# lcd_duffle_pth_mk_6.net
KiCad netlist of a schematic drawn in EAGLE
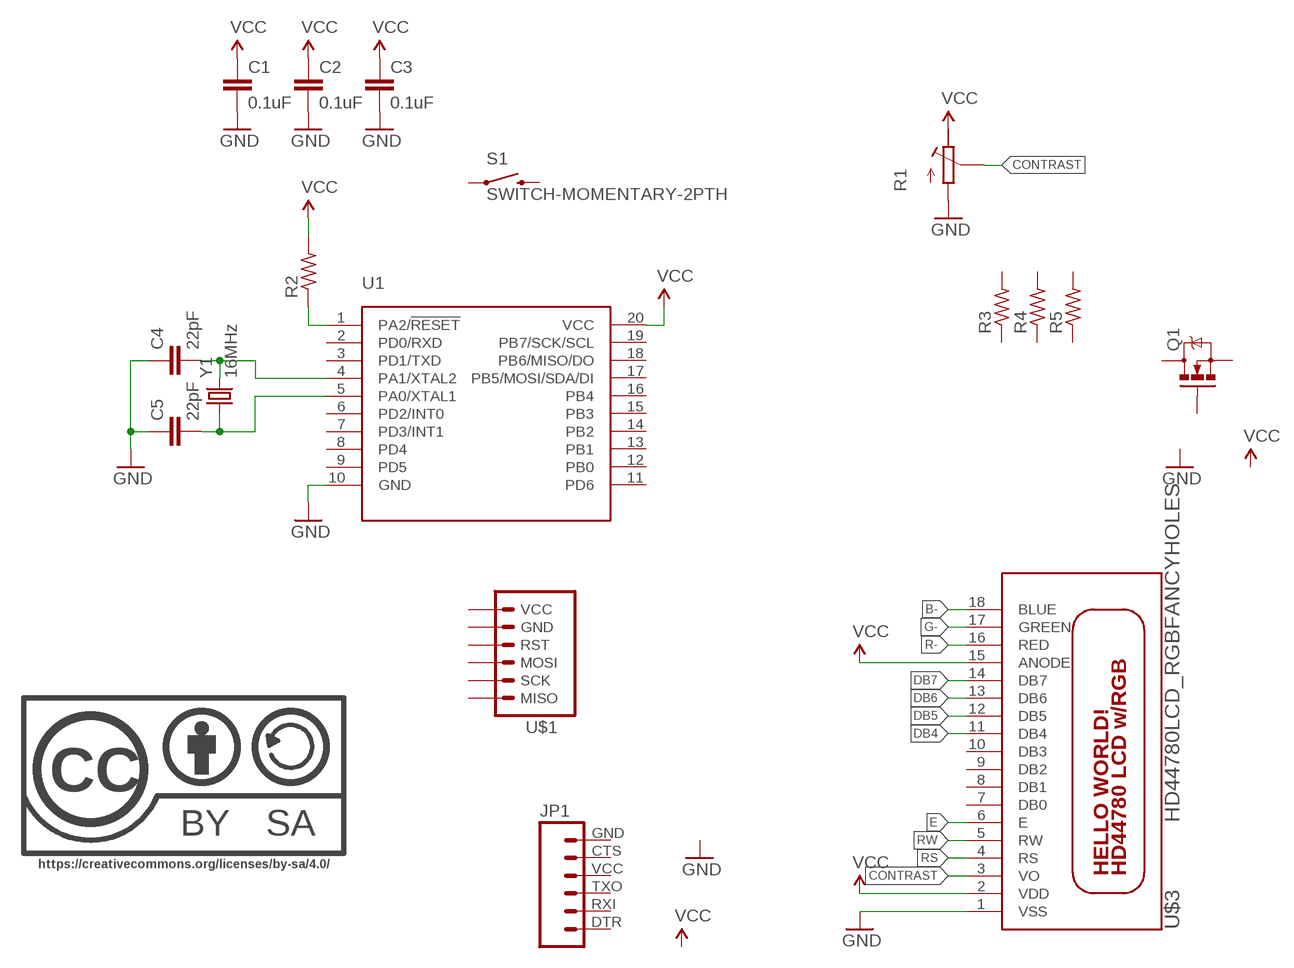
[diagram p0: schematic, sheet 1]

(export (version "E")
  (design (tool "Eeschema 10.0.6"))
  (components
    (comp (ref "C1")
      (value "0.1uF")
      (footprint "eagle-import:C025-024X044")
      (libsource (lib "eagle-import") (part "CAPACITOR-CERAMIC025-024X044"))
    )
    (comp (ref "C2")
      (value "0.1uF")
      (footprint "eagle-import:C025-024X044")
      (libsource (lib "eagle-import") (part "CAPACITOR-CERAMIC025-024X044"))
    )
    (comp (ref "C3")
      (value "0.1uF")
      (footprint "eagle-import:C025-024X044")
      (libsource (lib "eagle-import") (part "CAPACITOR-CERAMIC025-024X044"))
    )
    (comp (ref "C4")
      (value "22pF")
      (footprint "eagle-import:C025-024X044")
      (libsource (lib "eagle-import") (part "CAPACITOR-CERAMIC025-024X044"))
    )
    (comp (ref "C5")
      (value "22pF")
      (footprint "eagle-import:C025-024X044")
      (libsource (lib "eagle-import") (part "CAPACITOR-CERAMIC025-024X044"))
    )
    (comp (ref "JP1")
      (value "FTDI_BASICPTH-TINY-TEXT")
      (footprint "eagle-import:FTDI_TINY_TXT")
      (libsource (lib "eagle-import") (part "FTDI_BASICPTH-TINY-TEXT"))
    )
    (comp (ref "Q1")
      (value "MOSFET-NCHANNEL2N7000")
      (footprint "eagle-import:TO-92")
      (libsource (lib "eagle-import") (part "MOSFET-NCHANNEL2N7000"))
    )
    (comp (ref "R1")
      (value "POTENTIOMETERTHUMBWHEEL-16MM")
      (footprint "eagle-import:POT-THUMBWHEEL")
      (libsource (lib "eagle-import") (part "POTENTIOMETERTHUMBWHEEL-16MM"))
    )
    (comp (ref "R2")
      (value "RESISTORPTH-AXIAL-6.35MM")
      (footprint "eagle-import:RESISTOR-AXIAL-PTH-6.35MM")
      (libsource (lib "eagle-import") (part "RESISTORPTH-AXIAL-6.35MM"))
    )
    (comp (ref "R3")
      (value "RESISTORPTH-AXIAL-6.35MM")
      (footprint "eagle-import:RESISTOR-AXIAL-PTH-6.35MM")
      (libsource (lib "eagle-import") (part "RESISTORPTH-AXIAL-6.35MM"))
    )
    (comp (ref "R4")
      (value "RESISTORPTH-AXIAL-6.35MM")
      (footprint "eagle-import:RESISTOR-AXIAL-PTH-6.35MM")
      (libsource (lib "eagle-import") (part "RESISTORPTH-AXIAL-6.35MM"))
    )
    (comp (ref "R5")
      (value "RESISTORPTH-AXIAL-6.35MM")
      (footprint "eagle-import:RESISTOR-AXIAL-PTH-6.35MM")
      (libsource (lib "eagle-import") (part "RESISTORPTH-AXIAL-6.35MM"))
    )
    (comp (ref "S1")
      (value "SWITCH-MOMENTARY-2PTH")
      (footprint "eagle-import:TACTILE-PTH")
      (libsource (lib "eagle-import") (part "SWITCH-MOMENTARY-2PTH"))
    )
    (comp (ref "U$1")
      (value "AVR_MINI_PROGJST-XH-RA-PTH")
      (footprint "eagle-import:AVR_MINI_PROG_JST_XH_RA")
      (libsource (lib "eagle-import") (part "AVR_MINI_PROGJST-XH-RA-PTH"))
    )
    (comp (ref "U$2")
      (value "CC-BY-SA-4.0NO-URL")
      (footprint "eagle-import:CC-BY-SA-4.0-NO-URL")
      (libsource (lib "eagle-import") (part "CC-BY-SA-4.0NO-URL"))
    )
    (comp (ref "U$3")
      (value "HD44780LCD_RGBFANCYHOLES")
      (footprint "eagle-import:LCD1602-RGB-CENTERED-MARKEDHOLES")
      (libsource (lib "eagle-import") (part "HD44780LCD_RGBFANCYHOLES"))
    )
    (comp (ref "U1")
      (value "ATTINY2313ADIP")
      (footprint "eagle-import:DIL20")
      (libsource (lib "eagle-import") (part "ATTINY2313ADIP"))
    )
    (comp (ref "Y1")
      (value "16MHz")
      (footprint "eagle-import:HC49U-V")
      (libsource (lib "eagle-import") (part "CRYSTALHC49UV"))
    )
  )
  (nets
    (net (code "1") (name "B-") (class "Default")
      (node (ref "U$3") (pin "18") (pinfunction "BLUE_18") (pintype "input"))
    )
    (net (code "2") (name "CONTRAST") (class "Default")
      (node (ref "R1") (pin "2") (pinfunction "S_2") (pintype "passive"))
      (node (ref "R1") (pin "2@1") (pinfunction "S_2@1") (pintype "passive"))
      (node (ref "U$3") (pin "3") (pinfunction "VO_3") (pintype "input"))
    )
    (net (code "3") (name "DB4") (class "Default")
      (node (ref "U$3") (pin "11") (pinfunction "DB4_11") (pintype "bidirectional"))
    )
    (net (code "4") (name "DB5") (class "Default")
      (node (ref "U$3") (pin "12") (pinfunction "DB5_12") (pintype "bidirectional"))
    )
    (net (code "5") (name "DB6") (class "Default")
      (node (ref "U$3") (pin "13") (pinfunction "DB6_13") (pintype "bidirectional"))
    )
    (net (code "6") (name "DB7") (class "Default")
      (node (ref "U$3") (pin "14") (pinfunction "DB7_14") (pintype "bidirectional"))
    )
    (net (code "7") (name "E") (class "Default")
      (node (ref "U$3") (pin "6") (pinfunction "E_6") (pintype "input"))
    )
    (net (code "8") (name "G-") (class "Default")
      (node (ref "U$3") (pin "17") (pinfunction "GREEN_17") (pintype "input"))
    )
    (net (code "9") (name "GND") (class "Default")
      (node (ref "C1") (pin "2") (pinfunction "2_2") (pintype "passive"))
      (node (ref "C2") (pin "2") (pinfunction "2_2") (pintype "passive"))
      (node (ref "C3") (pin "2") (pinfunction "2_2") (pintype "passive"))
      (node (ref "C4") (pin "1") (pinfunction "1_1") (pintype "passive"))
      (node (ref "C5") (pin "1") (pinfunction "1_1") (pintype "passive"))
      (node (ref "R1") (pin "1") (pinfunction "A_1") (pintype "passive"))
      (node (ref "U$3") (pin "1") (pinfunction "VSS_1") (pintype "power_in"))
      (node (ref "U1") (pin "10") (pinfunction "GND_10") (pintype "bidirectional"))
    )
    (net (code "10") (name "Net-(R2-1)") (class "Default")
      (node (ref "R2") (pin "P$1") (pinfunction "1_P$1") (pintype "passive"))
      (node (ref "U1") (pin "1") (pinfunction "PA2/~{RESET}_1") (pintype "bidirectional"))
    )
    (net (code "11") (name "Net-(U1-PA0{slash}XTAL1)") (class "Default")
      (node (ref "C5") (pin "2") (pinfunction "2_2") (pintype "passive"))
      (node (ref "U1") (pin "5") (pinfunction "PA0/XTAL1_5") (pintype "bidirectional"))
      (node (ref "Y1") (pin "1") (pinfunction "1_1") (pintype "passive"))
    )
    (net (code "12") (name "Net-(U1-PA1{slash}XTAL2)") (class "Default")
      (node (ref "C4") (pin "2") (pinfunction "2_2") (pintype "passive"))
      (node (ref "U1") (pin "4") (pinfunction "PA1/XTAL2_4") (pintype "bidirectional"))
      (node (ref "Y1") (pin "2") (pinfunction "2_2") (pintype "passive"))
    )
    (net (code "13") (name "R-") (class "Default")
      (node (ref "U$3") (pin "16") (pinfunction "RED_16") (pintype "input"))
    )
    (net (code "14") (name "RS") (class "Default")
      (node (ref "U$3") (pin "4") (pinfunction "RS_4") (pintype "input"))
    )
    (net (code "15") (name "RW") (class "Default")
      (node (ref "U$3") (pin "5") (pinfunction "RW_5") (pintype "input"))
    )
    (net (code "16") (name "VCC") (class "Default")
      (node (ref "C1") (pin "1") (pinfunction "1_1") (pintype "passive"))
      (node (ref "C2") (pin "1") (pinfunction "1_1") (pintype "passive"))
      (node (ref "C3") (pin "1") (pinfunction "1_1") (pintype "passive"))
      (node (ref "R1") (pin "3") (pinfunction "E_3") (pintype "passive"))
      (node (ref "R2") (pin "P$2") (pinfunction "2_P$2") (pintype "passive"))
      (node (ref "U$3") (pin "15") (pinfunction "ANODE_15") (pintype "input"))
      (node (ref "U$3") (pin "2") (pinfunction "VDD_2") (pintype "power_in"))
      (node (ref "U1") (pin "20") (pinfunction "VCC_20") (pintype "bidirectional"))
    )
    (net (code "17") (name "unconnected-(JP1-1-PadDTR)") (class "Default")
      (node (ref "JP1") (pin "DTR") (pinfunction "1_DTR") (pintype "passive"))
    )
    (net (code "18") (name "unconnected-(JP1-2-PadRXI)") (class "Default")
      (node (ref "JP1") (pin "RXI") (pinfunction "2_RXI") (pintype "passive"))
    )
    (net (code "19") (name "unconnected-(JP1-3-PadTXO)") (class "Default")
      (node (ref "JP1") (pin "TXO") (pinfunction "3_TXO") (pintype "passive"))
    )
    (net (code "20") (name "unconnected-(JP1-4-PadVCC)") (class "Default")
      (node (ref "JP1") (pin "VCC") (pinfunction "4_VCC") (pintype "passive"))
    )
    (net (code "21") (name "unconnected-(JP1-5-PadCTS)") (class "Default")
      (node (ref "JP1") (pin "CTS") (pinfunction "5_CTS") (pintype "passive"))
    )
    (net (code "22") (name "unconnected-(JP1-6-PadGND)") (class "Default")
      (node (ref "JP1") (pin "GND") (pinfunction "6_GND") (pintype "passive"))
    )
    (net (code "23") (name "unconnected-(Q1-D-Pad3)") (class "Default")
      (node (ref "Q1") (pin "3") (pinfunction "D_3") (pintype "passive"))
    )
    (net (code "24") (name "unconnected-(Q1-G-Pad2)") (class "Default")
      (node (ref "Q1") (pin "2") (pinfunction "G_2") (pintype "passive"))
    )
    (net (code "25") (name "unconnected-(Q1-S-Pad1)") (class "Default")
      (node (ref "Q1") (pin "1") (pinfunction "S_1") (pintype "passive"))
    )
    (net (code "26") (name "unconnected-(R3-1-PadP$1)") (class "Default")
      (node (ref "R3") (pin "P$1") (pinfunction "1_P$1") (pintype "passive"))
    )
    (net (code "27") (name "unconnected-(R3-2-PadP$2)") (class "Default")
      (node (ref "R3") (pin "P$2") (pinfunction "2_P$2") (pintype "passive"))
    )
    (net (code "28") (name "unconnected-(R4-1-PadP$1)") (class "Default")
      (node (ref "R4") (pin "P$1") (pinfunction "1_P$1") (pintype "passive"))
    )
    (net (code "29") (name "unconnected-(R4-2-PadP$2)") (class "Default")
      (node (ref "R4") (pin "P$2") (pinfunction "2_P$2") (pintype "passive"))
    )
    (net (code "30") (name "unconnected-(R5-1-PadP$1)") (class "Default")
      (node (ref "R5") (pin "P$1") (pinfunction "1_P$1") (pintype "passive"))
    )
    (net (code "31") (name "unconnected-(R5-2-PadP$2)") (class "Default")
      (node (ref "R5") (pin "P$2") (pinfunction "2_P$2") (pintype "passive"))
    )
    (net (code "32") (name "unconnected-(S1-2-Pad3)") (class "Default")
      (node (ref "S1") (pin "3") (pinfunction "2_3") (pintype "passive"))
    )
    (net (code "33") (name "unconnected-(S1-Pad1)") (class "Default")
      (node (ref "S1") (pin "1") (pinfunction "1_1") (pintype "passive"))
    )
    (net (code "34") (name "unconnected-(U$1-GND-Pad6)") (class "Default")
      (node (ref "U$1") (pin "6") (pinfunction "GND_6") (pintype "passive"))
    )
    (net (code "35") (name "unconnected-(U$1-MISO-Pad1)") (class "Default")
      (node (ref "U$1") (pin "1") (pinfunction "MISO_1") (pintype "passive"))
    )
    (net (code "36") (name "unconnected-(U$1-MOSI-Pad4)") (class "Default")
      (node (ref "U$1") (pin "4") (pinfunction "MOSI_4") (pintype "passive"))
    )
    (net (code "37") (name "unconnected-(U$1-RST-Pad5)") (class "Default")
      (node (ref "U$1") (pin "5") (pinfunction "RST_5") (pintype "passive"))
    )
    (net (code "38") (name "unconnected-(U$1-SCK-Pad3)") (class "Default")
      (node (ref "U$1") (pin "3") (pinfunction "SCK_3") (pintype "passive"))
    )
    (net (code "39") (name "unconnected-(U$1-VCC-Pad2)") (class "Default")
      (node (ref "U$1") (pin "2") (pinfunction "VCC_2") (pintype "passive"))
    )
    (net (code "40") (name "unconnected-(U$3-DB0-Pad7)") (class "Default")
      (node (ref "U$3") (pin "7") (pinfunction "DB0_7") (pintype "bidirectional"))
    )
    (net (code "41") (name "unconnected-(U$3-DB1-Pad8)") (class "Default")
      (node (ref "U$3") (pin "8") (pinfunction "DB1_8") (pintype "bidirectional"))
    )
    (net (code "42") (name "unconnected-(U$3-DB2-Pad9)") (class "Default")
      (node (ref "U$3") (pin "9") (pinfunction "DB2_9") (pintype "bidirectional"))
    )
    (net (code "43") (name "unconnected-(U$3-DB3-Pad10)") (class "Default")
      (node (ref "U$3") (pin "10") (pinfunction "DB3_10") (pintype "bidirectional"))
    )
    (net (code "44") (name "unconnected-(U1-PB0-Pad12)") (class "Default")
      (node (ref "U1") (pin "12") (pinfunction "PB0_12") (pintype "bidirectional"))
    )
    (net (code "45") (name "unconnected-(U1-PB1-Pad13)") (class "Default")
      (node (ref "U1") (pin "13") (pinfunction "PB1_13") (pintype "bidirectional"))
    )
    (net (code "46") (name "unconnected-(U1-PB2-Pad14)") (class "Default")
      (node (ref "U1") (pin "14") (pinfunction "PB2_14") (pintype "bidirectional"))
    )
    (net (code "47") (name "unconnected-(U1-PB3-Pad15)") (class "Default")
      (node (ref "U1") (pin "15") (pinfunction "PB3_15") (pintype "bidirectional"))
    )
    (net (code "48") (name "unconnected-(U1-PB4-Pad16)") (class "Default")
      (node (ref "U1") (pin "16") (pinfunction "PB4_16") (pintype "bidirectional"))
    )
    (net (code "49") (name "unconnected-(U1-PB5{slash}MOSI{slash}SDA{slash}DI-Pad17)") (class "Default")
      (node (ref "U1") (pin "17") (pinfunction "PB5/MOSI/SDA/DI_17") (pintype "bidirectional"))
    )
    (net (code "50") (name "unconnected-(U1-PB6{slash}MISO{slash}DO-Pad18)") (class "Default")
      (node (ref "U1") (pin "18") (pinfunction "PB6/MISO/DO_18") (pintype "bidirectional"))
    )
    (net (code "51") (name "unconnected-(U1-PB7{slash}SCK{slash}SCL-Pad19)") (class "Default")
      (node (ref "U1") (pin "19") (pinfunction "PB7/SCK/SCL_19") (pintype "bidirectional"))
    )
    (net (code "52") (name "unconnected-(U1-PD0{slash}RXD-Pad2)") (class "Default")
      (node (ref "U1") (pin "2") (pinfunction "PD0/RXD_2") (pintype "bidirectional"))
    )
    (net (code "53") (name "unconnected-(U1-PD1{slash}TXD-Pad3)") (class "Default")
      (node (ref "U1") (pin "3") (pinfunction "PD1/TXD_3") (pintype "bidirectional"))
    )
    (net (code "54") (name "unconnected-(U1-PD2{slash}INT0-Pad6)") (class "Default")
      (node (ref "U1") (pin "6") (pinfunction "PD2/INT0_6") (pintype "bidirectional"))
    )
    (net (code "55") (name "unconnected-(U1-PD3{slash}INT1-Pad7)") (class "Default")
      (node (ref "U1") (pin "7") (pinfunction "PD3/INT1_7") (pintype "bidirectional"))
    )
    (net (code "56") (name "unconnected-(U1-PD4-Pad8)") (class "Default")
      (node (ref "U1") (pin "8") (pinfunction "PD4_8") (pintype "bidirectional"))
    )
    (net (code "57") (name "unconnected-(U1-PD5-Pad9)") (class "Default")
      (node (ref "U1") (pin "9") (pinfunction "PD5_9") (pintype "bidirectional"))
    )
    (net (code "58") (name "unconnected-(U1-PD6-Pad11)") (class "Default")
      (node (ref "U1") (pin "11") (pinfunction "PD6_11") (pintype "bidirectional"))
    )
  )
)
